# AccessPanelV2.net
KiCad netlist of a schematic drawn in EAGLE
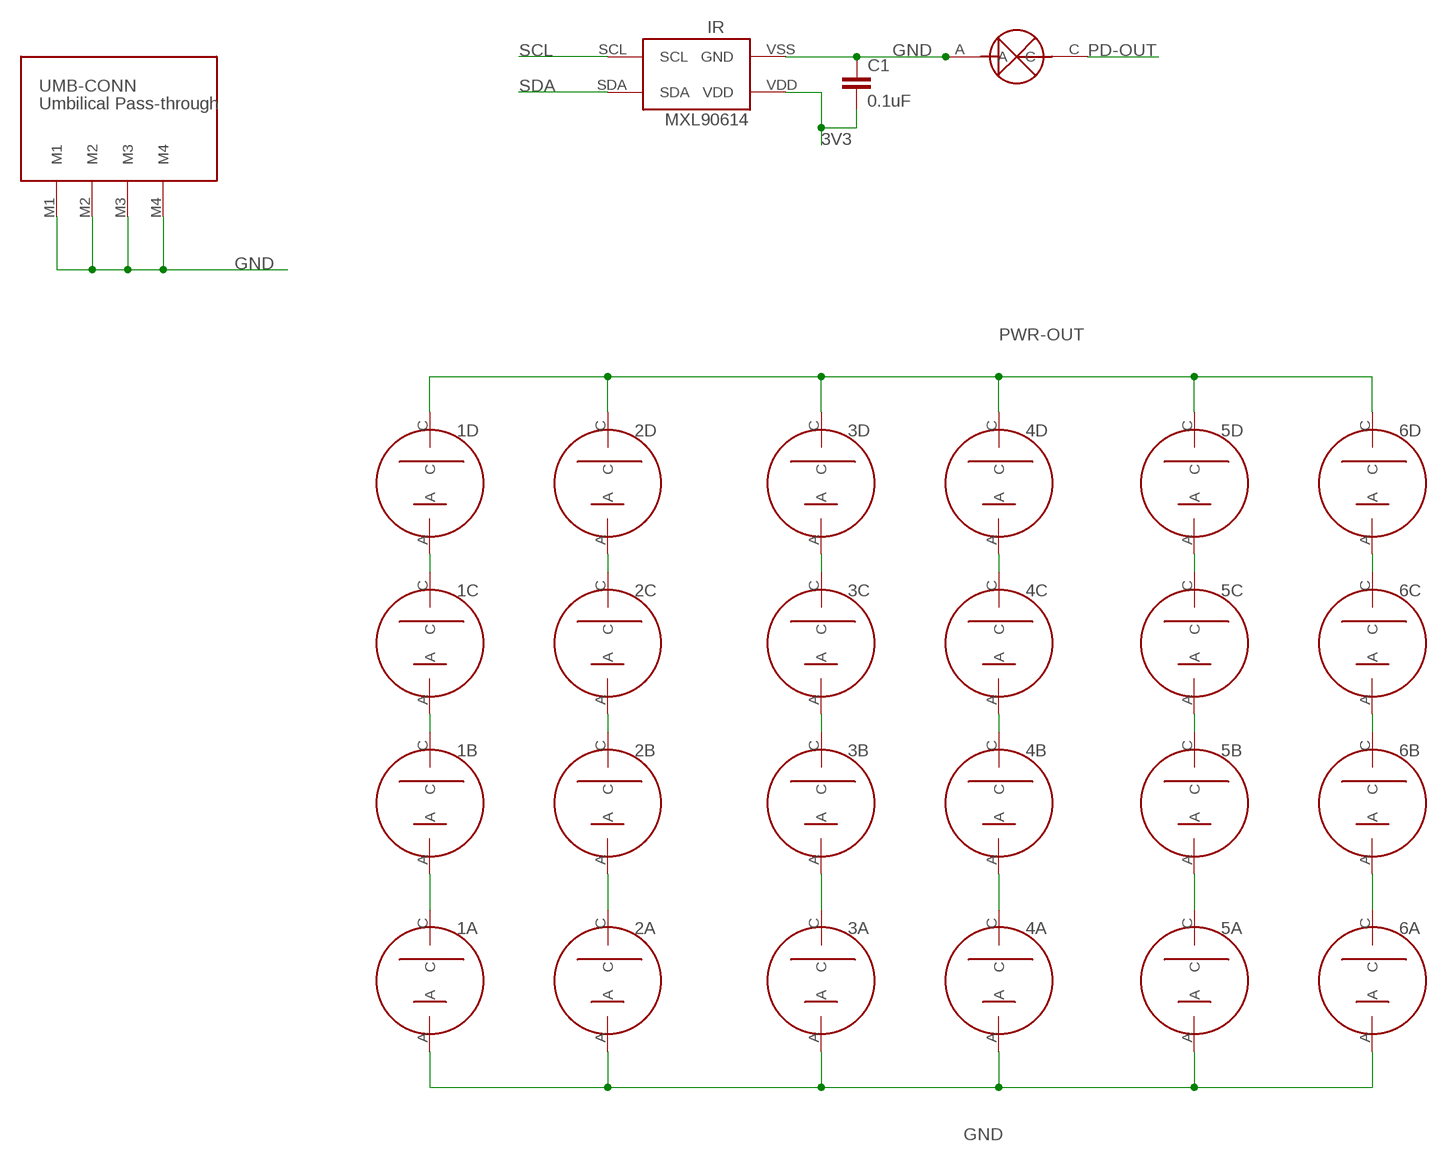
[diagram p0: schematic, sheet 1]

(export (version "E")
  (design (tool "Eeschema 10.0.6"))
  (components
    (comp (ref "1A")
      (value "NEWSOLARPANEL")
      (footprint "eagle-import:SOLARCELL2")
      (libsource (lib "eagle-import") (part "NEWSOLARPANEL"))
    )
    (comp (ref "1B")
      (value "NEWSOLARPANEL")
      (footprint "eagle-import:SOLARCELL2")
      (libsource (lib "eagle-import") (part "NEWSOLARPANEL"))
    )
    (comp (ref "1C")
      (value "NEWSOLARPANEL")
      (footprint "eagle-import:SOLARCELL2")
      (libsource (lib "eagle-import") (part "NEWSOLARPANEL"))
    )
    (comp (ref "1D")
      (value "NEWSOLARPANEL")
      (footprint "eagle-import:SOLARCELL2")
      (libsource (lib "eagle-import") (part "NEWSOLARPANEL"))
    )
    (comp (ref "2A")
      (value "NEWSOLARPANEL")
      (footprint "eagle-import:SOLARCELL2")
      (libsource (lib "eagle-import") (part "NEWSOLARPANEL"))
    )
    (comp (ref "2B")
      (value "NEWSOLARPANEL")
      (footprint "eagle-import:SOLARCELL2")
      (libsource (lib "eagle-import") (part "NEWSOLARPANEL"))
    )
    (comp (ref "2C")
      (value "NEWSOLARPANEL")
      (footprint "eagle-import:SOLARCELL2")
      (libsource (lib "eagle-import") (part "NEWSOLARPANEL"))
    )
    (comp (ref "2D")
      (value "NEWSOLARPANEL")
      (footprint "eagle-import:SOLARCELL2")
      (libsource (lib "eagle-import") (part "NEWSOLARPANEL"))
    )
    (comp (ref "3A")
      (value "NEWSOLARPANEL")
      (footprint "eagle-import:SOLARCELL2")
      (libsource (lib "eagle-import") (part "NEWSOLARPANEL"))
    )
    (comp (ref "3B")
      (value "NEWSOLARPANEL")
      (footprint "eagle-import:SOLARCELL2")
      (libsource (lib "eagle-import") (part "NEWSOLARPANEL"))
    )
    (comp (ref "3C")
      (value "NEWSOLARPANEL")
      (footprint "eagle-import:SOLARCELL2")
      (libsource (lib "eagle-import") (part "NEWSOLARPANEL"))
    )
    (comp (ref "3D")
      (value "NEWSOLARPANEL")
      (footprint "eagle-import:SOLARCELL2")
      (libsource (lib "eagle-import") (part "NEWSOLARPANEL"))
    )
    (comp (ref "4A")
      (value "NEWSOLARPANEL")
      (footprint "eagle-import:SOLARCELL2")
      (libsource (lib "eagle-import") (part "NEWSOLARPANEL"))
    )
    (comp (ref "4B")
      (value "NEWSOLARPANEL")
      (footprint "eagle-import:SOLARCELL2")
      (libsource (lib "eagle-import") (part "NEWSOLARPANEL"))
    )
    (comp (ref "4C")
      (value "NEWSOLARPANEL")
      (footprint "eagle-import:SOLARCELL2")
      (libsource (lib "eagle-import") (part "NEWSOLARPANEL"))
    )
    (comp (ref "4D")
      (value "NEWSOLARPANEL")
      (footprint "eagle-import:SOLARCELL2")
      (libsource (lib "eagle-import") (part "NEWSOLARPANEL"))
    )
    (comp (ref "5A")
      (value "NEWSOLARPANEL")
      (footprint "eagle-import:SOLARCELL2")
      (libsource (lib "eagle-import") (part "NEWSOLARPANEL"))
    )
    (comp (ref "5B")
      (value "NEWSOLARPANEL")
      (footprint "eagle-import:SOLARCELL2")
      (libsource (lib "eagle-import") (part "NEWSOLARPANEL"))
    )
    (comp (ref "5C")
      (value "NEWSOLARPANEL")
      (footprint "eagle-import:SOLARCELL2")
      (libsource (lib "eagle-import") (part "NEWSOLARPANEL"))
    )
    (comp (ref "5D")
      (value "NEWSOLARPANEL")
      (footprint "eagle-import:SOLARCELL2")
      (libsource (lib "eagle-import") (part "NEWSOLARPANEL"))
    )
    (comp (ref "6A")
      (value "NEWSOLARPANEL")
      (footprint "eagle-import:SOLARCELL2")
      (libsource (lib "eagle-import") (part "NEWSOLARPANEL"))
    )
    (comp (ref "6B")
      (value "NEWSOLARPANEL")
      (footprint "eagle-import:SOLARCELL2")
      (libsource (lib "eagle-import") (part "NEWSOLARPANEL"))
    )
    (comp (ref "6C")
      (value "NEWSOLARPANEL")
      (footprint "eagle-import:SOLARCELL2")
      (libsource (lib "eagle-import") (part "NEWSOLARPANEL"))
    )
    (comp (ref "6D")
      (value "NEWSOLARPANEL")
      (footprint "eagle-import:SOLARCELL2")
      (libsource (lib "eagle-import") (part "NEWSOLARPANEL"))
    )
    (comp (ref "C1")
      (value "0.1uF")
      (footprint "eagle-import:0805")
      (libsource (lib "eagle-import") (part "CAP0805"))
    )
    (comp (ref "IR")
      (value "MXL90620")
      (footprint "eagle-import:MXL90614")
      (libsource (lib "eagle-import") (part "MXL90620"))
    )
    (comp (ref "PD")
      (value "PHOTODETECTOR")
      (footprint "eagle-import:PHOTODECTORDEVICE2")
      (libsource (lib "eagle-import") (part "PHOTODETECTOR"))
    )
    (comp (ref "UMB-CONN")
      (value "811-004-002-XX-7-22")
      (footprint "eagle-import:811-004-002-XX-7-22")
      (libsource (lib "eagle-import") (part "811-004-002-XX-7-22"))
    )
  )
  (nets
    (net (code "1") (name "/3V3") (class "Default")
      (node (ref "C1") (pin "2") (pinfunction "2_2") (pintype "passive"))
      (node (ref "IR") (pin "VDD") (pinfunction "VDD_VDD") (pintype "bidirectional"))
    )
    (net (code "2") (name "/GND") (class "Default")
      (node (ref "1A") (pin "A") (pinfunction "A_A") (pintype "bidirectional"))
      (node (ref "2A") (pin "A") (pinfunction "A_A") (pintype "bidirectional"))
      (node (ref "3A") (pin "A") (pinfunction "A_A") (pintype "bidirectional"))
      (node (ref "4A") (pin "A") (pinfunction "A_A") (pintype "bidirectional"))
      (node (ref "5A") (pin "A") (pinfunction "A_A") (pintype "bidirectional"))
      (node (ref "6A") (pin "A") (pinfunction "A_A") (pintype "bidirectional"))
      (node (ref "C1") (pin "1") (pinfunction "1_1") (pintype "passive"))
      (node (ref "IR") (pin "VSS") (pinfunction "GND_VSS") (pintype "bidirectional"))
      (node (ref "PD") (pin "A") (pinfunction "A_A") (pintype "bidirectional"))
      (node (ref "UMB-CONN") (pin "M1") (pinfunction "M1_M1") (pintype "bidirectional"))
      (node (ref "UMB-CONN") (pin "M2") (pinfunction "M2_M2") (pintype "bidirectional"))
      (node (ref "UMB-CONN") (pin "M3") (pinfunction "M3_M3") (pintype "bidirectional"))
      (node (ref "UMB-CONN") (pin "M4") (pinfunction "M4_M4") (pintype "bidirectional"))
    )
    (net (code "3") (name "/PD-OUT") (class "Default")
      (node (ref "PD") (pin "C") (pinfunction "C_C") (pintype "bidirectional"))
    )
    (net (code "4") (name "/PWR-OUT") (class "Default")
      (node (ref "1D") (pin "C") (pinfunction "C_C") (pintype "bidirectional"))
      (node (ref "2D") (pin "C") (pinfunction "C_C") (pintype "bidirectional"))
      (node (ref "3D") (pin "C") (pinfunction "C_C") (pintype "bidirectional"))
      (node (ref "4D") (pin "C") (pinfunction "C_C") (pintype "bidirectional"))
      (node (ref "5D") (pin "C") (pinfunction "C_C") (pintype "bidirectional"))
      (node (ref "6D") (pin "C") (pinfunction "C_C") (pintype "bidirectional"))
    )
    (net (code "5") (name "/SCL") (class "Default")
      (node (ref "IR") (pin "SCL") (pinfunction "SCL_SCL") (pintype "bidirectional"))
    )
    (net (code "6") (name "/SDA") (class "Default")
      (node (ref "IR") (pin "SDA") (pinfunction "SDA_SDA") (pintype "bidirectional"))
    )
    (net (code "7") (name "Net-(1A-PadC)") (class "Default")
      (node (ref "1A") (pin "C") (pinfunction "C_C") (pintype "bidirectional"))
      (node (ref "1B") (pin "A") (pinfunction "A_A") (pintype "bidirectional"))
    )
    (net (code "8") (name "Net-(1B-PadC)") (class "Default")
      (node (ref "1B") (pin "C") (pinfunction "C_C") (pintype "bidirectional"))
      (node (ref "1C") (pin "A") (pinfunction "A_A") (pintype "bidirectional"))
    )
    (net (code "9") (name "Net-(1C-PadC)") (class "Default")
      (node (ref "1C") (pin "C") (pinfunction "C_C") (pintype "bidirectional"))
      (node (ref "1D") (pin "A") (pinfunction "A_A") (pintype "bidirectional"))
    )
    (net (code "10") (name "Net-(2A-PadC)") (class "Default")
      (node (ref "2A") (pin "C") (pinfunction "C_C") (pintype "bidirectional"))
      (node (ref "2B") (pin "A") (pinfunction "A_A") (pintype "bidirectional"))
    )
    (net (code "11") (name "Net-(2B-PadC)") (class "Default")
      (node (ref "2B") (pin "C") (pinfunction "C_C") (pintype "bidirectional"))
      (node (ref "2C") (pin "A") (pinfunction "A_A") (pintype "bidirectional"))
    )
    (net (code "12") (name "Net-(2C-PadC)") (class "Default")
      (node (ref "2C") (pin "C") (pinfunction "C_C") (pintype "bidirectional"))
      (node (ref "2D") (pin "A") (pinfunction "A_A") (pintype "bidirectional"))
    )
    (net (code "13") (name "Net-(3A-PadC)") (class "Default")
      (node (ref "3A") (pin "C") (pinfunction "C_C") (pintype "bidirectional"))
      (node (ref "3B") (pin "A") (pinfunction "A_A") (pintype "bidirectional"))
    )
    (net (code "14") (name "Net-(3B-PadC)") (class "Default")
      (node (ref "3B") (pin "C") (pinfunction "C_C") (pintype "bidirectional"))
      (node (ref "3C") (pin "A") (pinfunction "A_A") (pintype "bidirectional"))
    )
    (net (code "15") (name "Net-(3C-PadC)") (class "Default")
      (node (ref "3C") (pin "C") (pinfunction "C_C") (pintype "bidirectional"))
      (node (ref "3D") (pin "A") (pinfunction "A_A") (pintype "bidirectional"))
    )
    (net (code "16") (name "Net-(4A-PadC)") (class "Default")
      (node (ref "4A") (pin "C") (pinfunction "C_C") (pintype "bidirectional"))
      (node (ref "4B") (pin "A") (pinfunction "A_A") (pintype "bidirectional"))
    )
    (net (code "17") (name "Net-(4B-PadC)") (class "Default")
      (node (ref "4B") (pin "C") (pinfunction "C_C") (pintype "bidirectional"))
      (node (ref "4C") (pin "A") (pinfunction "A_A") (pintype "bidirectional"))
    )
    (net (code "18") (name "Net-(4C-PadC)") (class "Default")
      (node (ref "4C") (pin "C") (pinfunction "C_C") (pintype "bidirectional"))
      (node (ref "4D") (pin "A") (pinfunction "A_A") (pintype "bidirectional"))
    )
    (net (code "19") (name "Net-(5A-PadC)") (class "Default")
      (node (ref "5A") (pin "C") (pinfunction "C_C") (pintype "bidirectional"))
      (node (ref "5B") (pin "A") (pinfunction "A_A") (pintype "bidirectional"))
    )
    (net (code "20") (name "Net-(5B-PadC)") (class "Default")
      (node (ref "5B") (pin "C") (pinfunction "C_C") (pintype "bidirectional"))
      (node (ref "5C") (pin "A") (pinfunction "A_A") (pintype "bidirectional"))
    )
    (net (code "21") (name "Net-(5C-PadC)") (class "Default")
      (node (ref "5C") (pin "C") (pinfunction "C_C") (pintype "bidirectional"))
      (node (ref "5D") (pin "A") (pinfunction "A_A") (pintype "bidirectional"))
    )
    (net (code "22") (name "Net-(6A-PadC)") (class "Default")
      (node (ref "6A") (pin "C") (pinfunction "C_C") (pintype "bidirectional"))
      (node (ref "6B") (pin "A") (pinfunction "A_A") (pintype "bidirectional"))
    )
    (net (code "23") (name "Net-(6B-PadC)") (class "Default")
      (node (ref "6B") (pin "C") (pinfunction "C_C") (pintype "bidirectional"))
      (node (ref "6C") (pin "A") (pinfunction "A_A") (pintype "bidirectional"))
    )
    (net (code "24") (name "Net-(6C-PadC)") (class "Default")
      (node (ref "6C") (pin "C") (pinfunction "C_C") (pintype "bidirectional"))
      (node (ref "6D") (pin "A") (pinfunction "A_A") (pintype "bidirectional"))
    )
  )
)
